# diode_keyboard.net
KiCad netlist of a schematic drawn in EAGLE
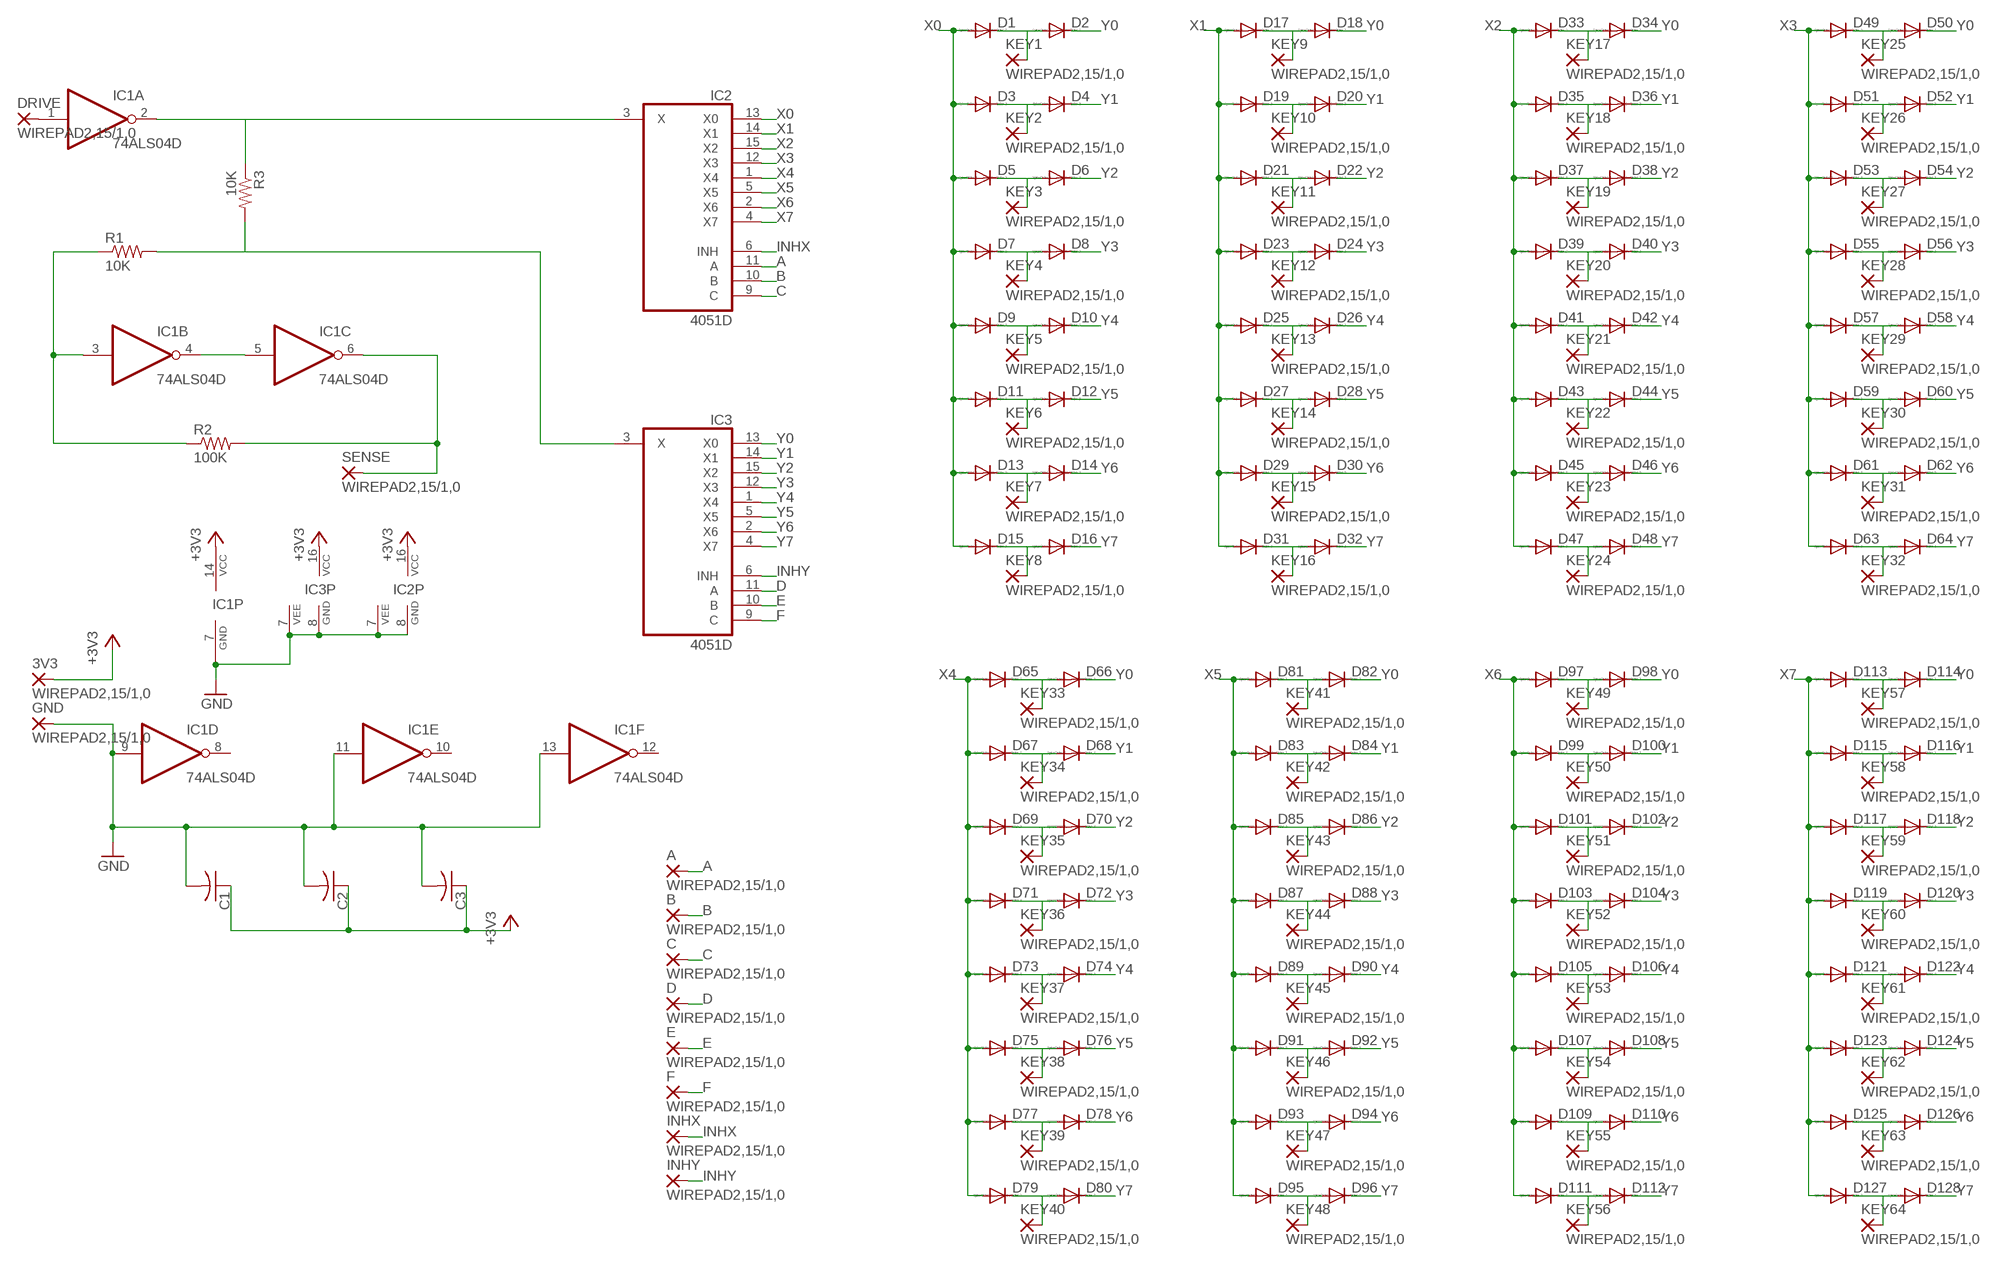
[diagram p0: schematic, sheet 1]

(export (version "E")
  (design (tool "Eeschema 10.0.6"))
  (components
    (comp (ref "3V3")
      (value "WIREPAD2,15/1,0")
      (footprint "eagle-import:2,15_1,0")
      (libsource (lib "eagle-import") (part "WIREPAD2,15/1,0"))
    )
    (comp (ref "A")
      (value "WIREPAD2,15/1,0")
      (footprint "eagle-import:2,15_1,0")
      (libsource (lib "eagle-import") (part "WIREPAD2,15/1,0"))
    )
    (comp (ref "B")
      (value "WIREPAD2,15/1,0")
      (footprint "eagle-import:2,15_1,0")
      (libsource (lib "eagle-import") (part "WIREPAD2,15/1,0"))
    )
    (comp (ref "C")
      (value "WIREPAD2,15/1,0")
      (footprint "eagle-import:2,15_1,0")
      (libsource (lib "eagle-import") (part "WIREPAD2,15/1,0"))
    )
    (comp (ref "C1")
      (value "C-US025-024X044")
      (footprint "eagle-import:C025-024X044")
      (libsource (lib "eagle-import") (part "C-US025-024X044"))
    )
    (comp (ref "C2")
      (value "C-US025-024X044")
      (footprint "eagle-import:C025-024X044")
      (libsource (lib "eagle-import") (part "C-US025-024X044"))
    )
    (comp (ref "C3")
      (value "C-US025-024X044")
      (footprint "eagle-import:C025-024X044")
      (libsource (lib "eagle-import") (part "C-US025-024X044"))
    )
    (comp (ref "D")
      (value "WIREPAD2,15/1,0")
      (footprint "eagle-import:2,15_1,0")
      (libsource (lib "eagle-import") (part "WIREPAD2,15/1,0"))
    )
    (comp (ref "D1")
      (value "DIODE-D-2.5")
      (footprint "eagle-import:D-2.5")
      (libsource (lib "eagle-import") (part "DIODE-D-2.5"))
    )
    (comp (ref "D2")
      (value "DIODE-D-2.5")
      (footprint "eagle-import:D-2.5")
      (libsource (lib "eagle-import") (part "DIODE-D-2.5"))
    )
    (comp (ref "D3")
      (value "DIODE-D-2.5")
      (footprint "eagle-import:D-2.5")
      (libsource (lib "eagle-import") (part "DIODE-D-2.5"))
    )
    (comp (ref "D4")
      (value "DIODE-D-2.5")
      (footprint "eagle-import:D-2.5")
      (libsource (lib "eagle-import") (part "DIODE-D-2.5"))
    )
    (comp (ref "D5")
      (value "DIODE-D-2.5")
      (footprint "eagle-import:D-2.5")
      (libsource (lib "eagle-import") (part "DIODE-D-2.5"))
    )
    (comp (ref "D6")
      (value "DIODE-D-2.5")
      (footprint "eagle-import:D-2.5")
      (libsource (lib "eagle-import") (part "DIODE-D-2.5"))
    )
    (comp (ref "D7")
      (value "DIODE-D-2.5")
      (footprint "eagle-import:D-2.5")
      (libsource (lib "eagle-import") (part "DIODE-D-2.5"))
    )
    (comp (ref "D8")
      (value "DIODE-D-2.5")
      (footprint "eagle-import:D-2.5")
      (libsource (lib "eagle-import") (part "DIODE-D-2.5"))
    )
    (comp (ref "D9")
      (value "DIODE-D-2.5")
      (footprint "eagle-import:D-2.5")
      (libsource (lib "eagle-import") (part "DIODE-D-2.5"))
    )
    (comp (ref "D10")
      (value "DIODE-D-2.5")
      (footprint "eagle-import:D-2.5")
      (libsource (lib "eagle-import") (part "DIODE-D-2.5"))
    )
    (comp (ref "D11")
      (value "DIODE-D-2.5")
      (footprint "eagle-import:D-2.5")
      (libsource (lib "eagle-import") (part "DIODE-D-2.5"))
    )
    (comp (ref "D12")
      (value "DIODE-D-2.5")
      (footprint "eagle-import:D-2.5")
      (libsource (lib "eagle-import") (part "DIODE-D-2.5"))
    )
    (comp (ref "D13")
      (value "DIODE-D-2.5")
      (footprint "eagle-import:D-2.5")
      (libsource (lib "eagle-import") (part "DIODE-D-2.5"))
    )
    (comp (ref "D14")
      (value "DIODE-D-2.5")
      (footprint "eagle-import:D-2.5")
      (libsource (lib "eagle-import") (part "DIODE-D-2.5"))
    )
    (comp (ref "D15")
      (value "DIODE-D-2.5")
      (footprint "eagle-import:D-2.5")
      (libsource (lib "eagle-import") (part "DIODE-D-2.5"))
    )
    (comp (ref "D16")
      (value "DIODE-D-2.5")
      (footprint "eagle-import:D-2.5")
      (libsource (lib "eagle-import") (part "DIODE-D-2.5"))
    )
    (comp (ref "D17")
      (value "DIODE-D-2.5")
      (footprint "eagle-import:D-2.5")
      (libsource (lib "eagle-import") (part "DIODE-D-2.5"))
    )
    (comp (ref "D18")
      (value "DIODE-D-2.5")
      (footprint "eagle-import:D-2.5")
      (libsource (lib "eagle-import") (part "DIODE-D-2.5"))
    )
    (comp (ref "D19")
      (value "DIODE-D-2.5")
      (footprint "eagle-import:D-2.5")
      (libsource (lib "eagle-import") (part "DIODE-D-2.5"))
    )
    (comp (ref "D20")
      (value "DIODE-D-2.5")
      (footprint "eagle-import:D-2.5")
      (libsource (lib "eagle-import") (part "DIODE-D-2.5"))
    )
    (comp (ref "D21")
      (value "DIODE-D-2.5")
      (footprint "eagle-import:D-2.5")
      (libsource (lib "eagle-import") (part "DIODE-D-2.5"))
    )
    (comp (ref "D22")
      (value "DIODE-D-2.5")
      (footprint "eagle-import:D-2.5")
      (libsource (lib "eagle-import") (part "DIODE-D-2.5"))
    )
    (comp (ref "D23")
      (value "DIODE-D-2.5")
      (footprint "eagle-import:D-2.5")
      (libsource (lib "eagle-import") (part "DIODE-D-2.5"))
    )
    (comp (ref "D24")
      (value "DIODE-D-2.5")
      (footprint "eagle-import:D-2.5")
      (libsource (lib "eagle-import") (part "DIODE-D-2.5"))
    )
    (comp (ref "D25")
      (value "DIODE-D-2.5")
      (footprint "eagle-import:D-2.5")
      (libsource (lib "eagle-import") (part "DIODE-D-2.5"))
    )
    (comp (ref "D26")
      (value "DIODE-D-2.5")
      (footprint "eagle-import:D-2.5")
      (libsource (lib "eagle-import") (part "DIODE-D-2.5"))
    )
    (comp (ref "D27")
      (value "DIODE-D-2.5")
      (footprint "eagle-import:D-2.5")
      (libsource (lib "eagle-import") (part "DIODE-D-2.5"))
    )
    (comp (ref "D28")
      (value "DIODE-D-2.5")
      (footprint "eagle-import:D-2.5")
      (libsource (lib "eagle-import") (part "DIODE-D-2.5"))
    )
    (comp (ref "D29")
      (value "DIODE-D-2.5")
      (footprint "eagle-import:D-2.5")
      (libsource (lib "eagle-import") (part "DIODE-D-2.5"))
    )
    (comp (ref "D30")
      (value "DIODE-D-2.5")
      (footprint "eagle-import:D-2.5")
      (libsource (lib "eagle-import") (part "DIODE-D-2.5"))
    )
    (comp (ref "D31")
      (value "DIODE-D-2.5")
      (footprint "eagle-import:D-2.5")
      (libsource (lib "eagle-import") (part "DIODE-D-2.5"))
    )
    (comp (ref "D32")
      (value "DIODE-D-2.5")
      (footprint "eagle-import:D-2.5")
      (libsource (lib "eagle-import") (part "DIODE-D-2.5"))
    )
    (comp (ref "D33")
      (value "DIODE-D-2.5")
      (footprint "eagle-import:D-2.5")
      (libsource (lib "eagle-import") (part "DIODE-D-2.5"))
    )
    (comp (ref "D34")
      (value "DIODE-D-2.5")
      (footprint "eagle-import:D-2.5")
      (libsource (lib "eagle-import") (part "DIODE-D-2.5"))
    )
    (comp (ref "D35")
      (value "DIODE-D-2.5")
      (footprint "eagle-import:D-2.5")
      (libsource (lib "eagle-import") (part "DIODE-D-2.5"))
    )
    (comp (ref "D36")
      (value "DIODE-D-2.5")
      (footprint "eagle-import:D-2.5")
      (libsource (lib "eagle-import") (part "DIODE-D-2.5"))
    )
    (comp (ref "D37")
      (value "DIODE-D-2.5")
      (footprint "eagle-import:D-2.5")
      (libsource (lib "eagle-import") (part "DIODE-D-2.5"))
    )
    (comp (ref "D38")
      (value "DIODE-D-2.5")
      (footprint "eagle-import:D-2.5")
      (libsource (lib "eagle-import") (part "DIODE-D-2.5"))
    )
    (comp (ref "D39")
      (value "DIODE-D-2.5")
      (footprint "eagle-import:D-2.5")
      (libsource (lib "eagle-import") (part "DIODE-D-2.5"))
    )
    (comp (ref "D40")
      (value "DIODE-D-2.5")
      (footprint "eagle-import:D-2.5")
      (libsource (lib "eagle-import") (part "DIODE-D-2.5"))
    )
    (comp (ref "D41")
      (value "DIODE-D-2.5")
      (footprint "eagle-import:D-2.5")
      (libsource (lib "eagle-import") (part "DIODE-D-2.5"))
    )
    (comp (ref "D42")
      (value "DIODE-D-2.5")
      (footprint "eagle-import:D-2.5")
      (libsource (lib "eagle-import") (part "DIODE-D-2.5"))
    )
    (comp (ref "D43")
      (value "DIODE-D-2.5")
      (footprint "eagle-import:D-2.5")
      (libsource (lib "eagle-import") (part "DIODE-D-2.5"))
    )
    (comp (ref "D44")
      (value "DIODE-D-2.5")
      (footprint "eagle-import:D-2.5")
      (libsource (lib "eagle-import") (part "DIODE-D-2.5"))
    )
    (comp (ref "D45")
      (value "DIODE-D-2.5")
      (footprint "eagle-import:D-2.5")
      (libsource (lib "eagle-import") (part "DIODE-D-2.5"))
    )
    (comp (ref "D46")
      (value "DIODE-D-2.5")
      (footprint "eagle-import:D-2.5")
      (libsource (lib "eagle-import") (part "DIODE-D-2.5"))
    )
    (comp (ref "D47")
      (value "DIODE-D-2.5")
      (footprint "eagle-import:D-2.5")
      (libsource (lib "eagle-import") (part "DIODE-D-2.5"))
    )
    (comp (ref "D48")
      (value "DIODE-D-2.5")
      (footprint "eagle-import:D-2.5")
      (libsource (lib "eagle-import") (part "DIODE-D-2.5"))
    )
    (comp (ref "D49")
      (value "DIODE-D-2.5")
      (footprint "eagle-import:D-2.5")
      (libsource (lib "eagle-import") (part "DIODE-D-2.5"))
    )
    (comp (ref "D50")
      (value "DIODE-D-2.5")
      (footprint "eagle-import:D-2.5")
      (libsource (lib "eagle-import") (part "DIODE-D-2.5"))
    )
    (comp (ref "D51")
      (value "DIODE-D-2.5")
      (footprint "eagle-import:D-2.5")
      (libsource (lib "eagle-import") (part "DIODE-D-2.5"))
    )
    (comp (ref "D52")
      (value "DIODE-D-2.5")
      (footprint "eagle-import:D-2.5")
      (libsource (lib "eagle-import") (part "DIODE-D-2.5"))
    )
    (comp (ref "D53")
      (value "DIODE-D-2.5")
      (footprint "eagle-import:D-2.5")
      (libsource (lib "eagle-import") (part "DIODE-D-2.5"))
    )
    (comp (ref "D54")
      (value "DIODE-D-2.5")
      (footprint "eagle-import:D-2.5")
      (libsource (lib "eagle-import") (part "DIODE-D-2.5"))
    )
    (comp (ref "D55")
      (value "DIODE-D-2.5")
      (footprint "eagle-import:D-2.5")
      (libsource (lib "eagle-import") (part "DIODE-D-2.5"))
    )
    (comp (ref "D56")
      (value "DIODE-D-2.5")
      (footprint "eagle-import:D-2.5")
      (libsource (lib "eagle-import") (part "DIODE-D-2.5"))
    )
    (comp (ref "D57")
      (value "DIODE-D-2.5")
      (footprint "eagle-import:D-2.5")
      (libsource (lib "eagle-import") (part "DIODE-D-2.5"))
    )
    (comp (ref "D58")
      (value "DIODE-D-2.5")
      (footprint "eagle-import:D-2.5")
      (libsource (lib "eagle-import") (part "DIODE-D-2.5"))
    )
    (comp (ref "D59")
      (value "DIODE-D-2.5")
      (footprint "eagle-import:D-2.5")
      (libsource (lib "eagle-import") (part "DIODE-D-2.5"))
    )
    (comp (ref "D60")
      (value "DIODE-D-2.5")
      (footprint "eagle-import:D-2.5")
      (libsource (lib "eagle-import") (part "DIODE-D-2.5"))
    )
    (comp (ref "D61")
      (value "DIODE-D-2.5")
      (footprint "eagle-import:D-2.5")
      (libsource (lib "eagle-import") (part "DIODE-D-2.5"))
    )
    (comp (ref "D62")
      (value "DIODE-D-2.5")
      (footprint "eagle-import:D-2.5")
      (libsource (lib "eagle-import") (part "DIODE-D-2.5"))
    )
    (comp (ref "D63")
      (value "DIODE-D-2.5")
      (footprint "eagle-import:D-2.5")
      (libsource (lib "eagle-import") (part "DIODE-D-2.5"))
    )
    (comp (ref "D64")
      (value "DIODE-D-2.5")
      (footprint "eagle-import:D-2.5")
      (libsource (lib "eagle-import") (part "DIODE-D-2.5"))
    )
    (comp (ref "D65")
      (value "DIODE-D-2.5")
      (footprint "eagle-import:D-2.5")
      (libsource (lib "eagle-import") (part "DIODE-D-2.5"))
    )
    (comp (ref "D66")
      (value "DIODE-D-2.5")
      (footprint "eagle-import:D-2.5")
      (libsource (lib "eagle-import") (part "DIODE-D-2.5"))
    )
    (comp (ref "D67")
      (value "DIODE-D-2.5")
      (footprint "eagle-import:D-2.5")
      (libsource (lib "eagle-import") (part "DIODE-D-2.5"))
    )
    (comp (ref "D68")
      (value "DIODE-D-2.5")
      (footprint "eagle-import:D-2.5")
      (libsource (lib "eagle-import") (part "DIODE-D-2.5"))
    )
    (comp (ref "D69")
      (value "DIODE-D-2.5")
      (footprint "eagle-import:D-2.5")
      (libsource (lib "eagle-import") (part "DIODE-D-2.5"))
    )
    (comp (ref "D70")
      (value "DIODE-D-2.5")
      (footprint "eagle-import:D-2.5")
      (libsource (lib "eagle-import") (part "DIODE-D-2.5"))
    )
    (comp (ref "D71")
      (value "DIODE-D-2.5")
      (footprint "eagle-import:D-2.5")
      (libsource (lib "eagle-import") (part "DIODE-D-2.5"))
    )
    (comp (ref "D72")
      (value "DIODE-D-2.5")
      (footprint "eagle-import:D-2.5")
      (libsource (lib "eagle-import") (part "DIODE-D-2.5"))
    )
    (comp (ref "D73")
      (value "DIODE-D-2.5")
      (footprint "eagle-import:D-2.5")
      (libsource (lib "eagle-import") (part "DIODE-D-2.5"))
    )
    (comp (ref "D74")
      (value "DIODE-D-2.5")
      (footprint "eagle-import:D-2.5")
      (libsource (lib "eagle-import") (part "DIODE-D-2.5"))
    )
    (comp (ref "D75")
      (value "DIODE-D-2.5")
      (footprint "eagle-import:D-2.5")
      (libsource (lib "eagle-import") (part "DIODE-D-2.5"))
    )
    (comp (ref "D76")
      (value "DIODE-D-2.5")
      (footprint "eagle-import:D-2.5")
      (libsource (lib "eagle-import") (part "DIODE-D-2.5"))
    )
    (comp (ref "D77")
      (value "DIODE-D-2.5")
      (footprint "eagle-import:D-2.5")
      (libsource (lib "eagle-import") (part "DIODE-D-2.5"))
    )
    (comp (ref "D78")
      (value "DIODE-D-2.5")
      (footprint "eagle-import:D-2.5")
      (libsource (lib "eagle-import") (part "DIODE-D-2.5"))
    )
    (comp (ref "D79")
      (value "DIODE-D-2.5")
      (footprint "eagle-import:D-2.5")
      (libsource (lib "eagle-import") (part "DIODE-D-2.5"))
    )
    (comp (ref "D80")
      (value "DIODE-D-2.5")
      (footprint "eagle-import:D-2.5")
      (libsource (lib "eagle-import") (part "DIODE-D-2.5"))
    )
    (comp (ref "D81")
      (value "DIODE-D-2.5")
      (footprint "eagle-import:D-2.5")
      (libsource (lib "eagle-import") (part "DIODE-D-2.5"))
    )
    (comp (ref "D82")
      (value "DIODE-D-2.5")
      (footprint "eagle-import:D-2.5")
      (libsource (lib "eagle-import") (part "DIODE-D-2.5"))
    )
    (comp (ref "D83")
      (value "DIODE-D-2.5")
      (footprint "eagle-import:D-2.5")
      (libsource (lib "eagle-import") (part "DIODE-D-2.5"))
    )
    (comp (ref "D84")
      (value "DIODE-D-2.5")
      (footprint "eagle-import:D-2.5")
      (libsource (lib "eagle-import") (part "DIODE-D-2.5"))
    )
    (comp (ref "D85")
      (value "DIODE-D-2.5")
      (footprint "eagle-import:D-2.5")
      (libsource (lib "eagle-import") (part "DIODE-D-2.5"))
    )
    (comp (ref "D86")
      (value "DIODE-D-2.5")
      (footprint "eagle-import:D-2.5")
      (libsource (lib "eagle-import") (part "DIODE-D-2.5"))
    )
    (comp (ref "D87")
      (value "DIODE-D-2.5")
      (footprint "eagle-import:D-2.5")
      (libsource (lib "eagle-import") (part "DIODE-D-2.5"))
    )
    (comp (ref "D88")
      (value "DIODE-D-2.5")
      (footprint "eagle-import:D-2.5")
      (libsource (lib "eagle-import") (part "DIODE-D-2.5"))
    )
    (comp (ref "D89")
      (value "DIODE-D-2.5")
      (footprint "eagle-import:D-2.5")
      (libsource (lib "eagle-import") (part "DIODE-D-2.5"))
    )
    (comp (ref "D90")
      (value "DIODE-D-2.5")
      (footprint "eagle-import:D-2.5")
      (libsource (lib "eagle-import") (part "DIODE-D-2.5"))
    )
    (comp (ref "D91")
      (value "DIODE-D-2.5")
      (footprint "eagle-import:D-2.5")
      (libsource (lib "eagle-import") (part "DIODE-D-2.5"))
    )
    (comp (ref "D92")
      (value "DIODE-D-2.5")
      (footprint "eagle-import:D-2.5")
      (libsource (lib "eagle-import") (part "DIODE-D-2.5"))
    )
    (comp (ref "D93")
      (value "DIODE-D-2.5")
      (footprint "eagle-import:D-2.5")
      (libsource (lib "eagle-import") (part "DIODE-D-2.5"))
    )
    (comp (ref "D94")
      (value "DIODE-D-2.5")
      (footprint "eagle-import:D-2.5")
      (libsource (lib "eagle-import") (part "DIODE-D-2.5"))
    )
    (comp (ref "D95")
      (value "DIODE-D-2.5")
      (footprint "eagle-import:D-2.5")
      (libsource (lib "eagle-import") (part "DIODE-D-2.5"))
    )
    (comp (ref "D96")
      (value "DIODE-D-2.5")
      (footprint "eagle-import:D-2.5")
      (libsource (lib "eagle-import") (part "DIODE-D-2.5"))
    )
    (comp (ref "D97")
      (value "DIODE-D-2.5")
      (footprint "eagle-import:D-2.5")
      (libsource (lib "eagle-import") (part "DIODE-D-2.5"))
    )
    (comp (ref "D98")
      (value "DIODE-D-2.5")
      (footprint "eagle-import:D-2.5")
      (libsource (lib "eagle-import") (part "DIODE-D-2.5"))
    )
    (comp (ref "D99")
      (value "DIODE-D-2.5")
      (footprint "eagle-import:D-2.5")
      (libsource (lib "eagle-import") (part "DIODE-D-2.5"))
    )
    (comp (ref "D100")
      (value "DIODE-D-2.5")
      (footprint "eagle-import:D-2.5")
      (libsource (lib "eagle-import") (part "DIODE-D-2.5"))
    )
    (comp (ref "D101")
      (value "DIODE-D-2.5")
      (footprint "eagle-import:D-2.5")
      (libsource (lib "eagle-import") (part "DIODE-D-2.5"))
    )
    (comp (ref "D102")
      (value "DIODE-D-2.5")
      (footprint "eagle-import:D-2.5")
      (libsource (lib "eagle-import") (part "DIODE-D-2.5"))
    )
    (comp (ref "D103")
      (value "DIODE-D-2.5")
      (footprint "eagle-import:D-2.5")
      (libsource (lib "eagle-import") (part "DIODE-D-2.5"))
    )
    (comp (ref "D104")
      (value "DIODE-D-2.5")
      (footprint "eagle-import:D-2.5")
      (libsource (lib "eagle-import") (part "DIODE-D-2.5"))
    )
    (comp (ref "D105")
      (value "DIODE-D-2.5")
      (footprint "eagle-import:D-2.5")
      (libsource (lib "eagle-import") (part "DIODE-D-2.5"))
    )
    (comp (ref "D106")
      (value "DIODE-D-2.5")
      (footprint "eagle-import:D-2.5")
      (libsource (lib "eagle-import") (part "DIODE-D-2.5"))
    )
    (comp (ref "D107")
      (value "DIODE-D-2.5")
      (footprint "eagle-import:D-2.5")
      (libsource (lib "eagle-import") (part "DIODE-D-2.5"))
    )
    (comp (ref "D108")
      (value "DIODE-D-2.5")
      (footprint "eagle-import:D-2.5")
      (libsource (lib "eagle-import") (part "DIODE-D-2.5"))
    )
    (comp (ref "D109")
      (value "DIODE-D-2.5")
      (footprint "eagle-import:D-2.5")
      (libsource (lib "eagle-import") (part "DIODE-D-2.5"))
    )
    (comp (ref "D110")
      (value "DIODE-D-2.5")
      (footprint "eagle-import:D-2.5")
      (libsource (lib "eagle-import") (part "DIODE-D-2.5"))
    )
    (comp (ref "D111")
      (value "DIODE-D-2.5")
      (footprint "eagle-import:D-2.5")
      (libsource (lib "eagle-import") (part "DIODE-D-2.5"))
    )
    (comp (ref "D112")
      (value "DIODE-D-2.5")
      (footprint "eagle-import:D-2.5")
      (libsource (lib "eagle-import") (part "DIODE-D-2.5"))
    )
    (comp (ref "D113")
      (value "DIODE-D-2.5")
      (footprint "eagle-import:D-2.5")
      (libsource (lib "eagle-import") (part "DIODE-D-2.5"))
    )
    (comp (ref "D114")
      (value "DIODE-D-2.5")
      (footprint "eagle-import:D-2.5")
      (libsource (lib "eagle-import") (part "DIODE-D-2.5"))
    )
    (comp (ref "D115")
      (value "DIODE-D-2.5")
      (footprint "eagle-import:D-2.5")
      (libsource (lib "eagle-import") (part "DIODE-D-2.5"))
    )
    (comp (ref "D116")
      (value "DIODE-D-2.5")
      (footprint "eagle-import:D-2.5")
      (libsource (lib "eagle-import") (part "DIODE-D-2.5"))
    )
    (comp (ref "D117")
      (value "DIODE-D-2.5")
      (footprint "eagle-import:D-2.5")
      (libsource (lib "eagle-import") (part "DIODE-D-2.5"))
    )
    (comp (ref "D118")
      (value "DIODE-D-2.5")
      (footprint "eagle-import:D-2.5")
      (libsource (lib "eagle-import") (part "DIODE-D-2.5"))
    )
    (comp (ref "D119")
      (value "DIODE-D-2.5")
      (footprint "eagle-import:D-2.5")
      (libsource (lib "eagle-import") (part "DIODE-D-2.5"))
    )
    (comp (ref "D120")
      (value "DIODE-D-2.5")
      (footprint "eagle-import:D-2.5")
      (libsource (lib "eagle-import") (part "DIODE-D-2.5"))
    )
    (comp (ref "D121")
      (value "DIODE-D-2.5")
      (footprint "eagle-import:D-2.5")
      (libsource (lib "eagle-import") (part "DIODE-D-2.5"))
    )
    (comp (ref "D122")
      (value "DIODE-D-2.5")
      (footprint "eagle-import:D-2.5")
      (libsource (lib "eagle-import") (part "DIODE-D-2.5"))
    )
    (comp (ref "D123")
      (value "DIODE-D-2.5")
      (footprint "eagle-import:D-2.5")
      (libsource (lib "eagle-import") (part "DIODE-D-2.5"))
    )
    (comp (ref "D124")
      (value "DIODE-D-2.5")
      (footprint "eagle-import:D-2.5")
      (libsource (lib "eagle-import") (part "DIODE-D-2.5"))
    )
    (comp (ref "D125")
      (value "DIODE-D-2.5")
      (footprint "eagle-import:D-2.5")
      (libsource (lib "eagle-import") (part "DIODE-D-2.5"))
    )
    (comp (ref "D126")
      (value "DIODE-D-2.5")
      (footprint "eagle-import:D-2.5")
      (libsource (lib "eagle-import") (part "DIODE-D-2.5"))
    )
    (comp (ref "D127")
      (value "DIODE-D-2.5")
      (footprint "eagle-import:D-2.5")
      (libsource (lib "eagle-import") (part "DIODE-D-2.5"))
    )
    (comp (ref "D128")
      (value "DIODE-D-2.5")
      (footprint "eagle-import:D-2.5")
      (libsource (lib "eagle-import") (part "DIODE-D-2.5"))
    )
    (comp (ref "DRIVE")
      (value "WIREPAD2,15/1,0")
      (footprint "eagle-import:2,15_1,0")
      (libsource (lib "eagle-import") (part "WIREPAD2,15/1,0"))
    )
    (comp (ref "E")
      (value "WIREPAD2,15/1,0")
      (footprint "eagle-import:2,15_1,0")
      (libsource (lib "eagle-import") (part "WIREPAD2,15/1,0"))
    )
    (comp (ref "F")
      (value "WIREPAD2,15/1,0")
      (footprint "eagle-import:2,15_1,0")
      (libsource (lib "eagle-import") (part "WIREPAD2,15/1,0"))
    )
    (comp (ref "GND")
      (value "WIREPAD2,15/1,0")
      (footprint "eagle-import:2,15_1,0")
      (libsource (lib "eagle-import") (part "WIREPAD2,15/1,0"))
    )
    (comp (ref "IC1")
      (value "74ALS04D")
      (footprint "eagle-import:SO14")
      (libsource (lib "eagle-import") (part "7404DALS"))
    )
    (comp (ref "IC2")
      (value "4051D")
      (footprint "eagle-import:SO16")
      (libsource (lib "eagle-import") (part "4051D"))
    )
    (comp (ref "IC3")
      (value "4051D")
      (footprint "eagle-import:SO16")
      (libsource (lib "eagle-import") (part "4051D"))
    )
    (comp (ref "INHX")
      (value "WIREPAD2,15/1,0")
      (footprint "eagle-import:2,15_1,0")
      (libsource (lib "eagle-import") (part "WIREPAD2,15/1,0"))
    )
    (comp (ref "INHY")
      (value "WIREPAD2,15/1,0")
      (footprint "eagle-import:2,15_1,0")
      (libsource (lib "eagle-import") (part "WIREPAD2,15/1,0"))
    )
    (comp (ref "KEY1")
      (value "WIREPAD2,15/1,0")
      (footprint "eagle-import:2,15_1,0")
      (libsource (lib "eagle-import") (part "WIREPAD2,15/1,0"))
    )
    (comp (ref "KEY2")
      (value "WIREPAD2,15/1,0")
      (footprint "eagle-import:2,15_1,0")
      (libsource (lib "eagle-import") (part "WIREPAD2,15/1,0"))
    )
    (comp (ref "KEY3")
      (value "WIREPAD2,15/1,0")
      (footprint "eagle-import:2,15_1,0")
      (libsource (lib "eagle-import") (part "WIREPAD2,15/1,0"))
    )
    (comp (ref "KEY4")
      (value "WIREPAD2,15/1,0")
      (footprint "eagle-import:2,15_1,0")
      (libsource (lib "eagle-import") (part "WIREPAD2,15/1,0"))
    )
    (comp (ref "KEY5")
      (value "WIREPAD2,15/1,0")
      (footprint "eagle-import:2,15_1,0")
      (libsource (lib "eagle-import") (part "WIREPAD2,15/1,0"))
    )
    (comp (ref "KEY6")
      (value "WIREPAD2,15/1,0")
      (footprint "eagle-import:2,15_1,0")
      (libsource (lib "eagle-import") (part "WIREPAD2,15/1,0"))
    )
    (comp (ref "KEY7")
      (value "WIREPAD2,15/1,0")
      (footprint "eagle-import:2,15_1,0")
      (libsource (lib "eagle-import") (part "WIREPAD2,15/1,0"))
    )
    (comp (ref "KEY8")
      (value "WIREPAD2,15/1,0")
      (footprint "eagle-import:2,15_1,0")
      (libsource (lib "eagle-import") (part "WIREPAD2,15/1,0"))
    )
    (comp (ref "KEY9")
      (value "WIREPAD2,15/1,0")
      (footprint "eagle-import:2,15_1,0")
      (libsource (lib "eagle-import") (part "WIREPAD2,15/1,0"))
    )
    (comp (ref "KEY10")
      (value "WIREPAD2,15/1,0")
      (footprint "eagle-import:2,15_1,0")
      (libsource (lib "eagle-import") (part "WIREPAD2,15/1,0"))
    )
    (comp (ref "KEY11")
      (value "WIREPAD2,15/1,0")
      (footprint "eagle-import:2,15_1,0")
      (libsource (lib "eagle-import") (part "WIREPAD2,15/1,0"))
    )
    (comp (ref "KEY12")
      (value "WIREPAD2,15/1,0")
      (footprint "eagle-import:2,15_1,0")
      (libsource (lib "eagle-import") (part "WIREPAD2,15/1,0"))
    )
    (comp (ref "KEY13")
      (value "WIREPAD2,15/1,0")
      (footprint "eagle-import:2,15_1,0")
      (libsource (lib "eagle-import") (part "WIREPAD2,15/1,0"))
    )
    (comp (ref "KEY14")
      (value "WIREPAD2,15/1,0")
      (footprint "eagle-import:2,15_1,0")
      (libsource (lib "eagle-import") (part "WIREPAD2,15/1,0"))
    )
    (comp (ref "KEY15")
      (value "WIREPAD2,15/1,0")
      (footprint "eagle-import:2,15_1,0")
      (libsource (lib "eagle-import") (part "WIREPAD2,15/1,0"))
    )
    (comp (ref "KEY16")
      (value "WIREPAD2,15/1,0")
      (footprint "eagle-import:2,15_1,0")
      (libsource (lib "eagle-import") (part "WIREPAD2,15/1,0"))
    )
    (comp (ref "KEY17")
      (value "WIREPAD2,15/1,0")
      (footprint "eagle-import:2,15_1,0")
      (libsource (lib "eagle-import") (part "WIREPAD2,15/1,0"))
    )
    (comp (ref "KEY18")
      (value "WIREPAD2,15/1,0")
      (footprint "eagle-import:2,15_1,0")
      (libsource (lib "eagle-import") (part "WIREPAD2,15/1,0"))
    )
    (comp (ref "KEY19")
      (value "WIREPAD2,15/1,0")
      (footprint "eagle-import:2,15_1,0")
      (libsource (lib "eagle-import") (part "WIREPAD2,15/1,0"))
    )
    (comp (ref "KEY20")
      (value "WIREPAD2,15/1,0")
      (footprint "eagle-import:2,15_1,0")
      (libsource (lib "eagle-import") (part "WIREPAD2,15/1,0"))
    )
    (comp (ref "KEY21")
      (value "WIREPAD2,15/1,0")
      (footprint "eagle-import:2,15_1,0")
      (libsource (lib "eagle-import") (part "WIREPAD2,15/1,0"))
    )
    (comp (ref "KEY22")
      (value "WIREPAD2,15/1,0")
      (footprint "eagle-import:2,15_1,0")
      (libsource (lib "eagle-import") (part "WIREPAD2,15/1,0"))
    )
    (comp (ref "KEY23")
      (value "WIREPAD2,15/1,0")
      (footprint "eagle-import:2,15_1,0")
      (libsource (lib "eagle-import") (part "WIREPAD2,15/1,0"))
    )
    (comp (ref "KEY24")
      (value "WIREPAD2,15/1,0")
      (footprint "eagle-import:2,15_1,0")
      (libsource (lib "eagle-import") (part "WIREPAD2,15/1,0"))
    )
    (comp (ref "KEY25")
      (value "WIREPAD2,15/1,0")
      (footprint "eagle-import:2,15_1,0")
      (libsource (lib "eagle-import") (part "WIREPAD2,15/1,0"))
    )
    (comp (ref "KEY26")
      (value "WIREPAD2,15/1,0")
      (footprint "eagle-import:2,15_1,0")
      (libsource (lib "eagle-import") (part "WIREPAD2,15/1,0"))
    )
    (comp (ref "KEY27")
      (value "WIREPAD2,15/1,0")
      (footprint "eagle-import:2,15_1,0")
      (libsource (lib "eagle-import") (part "WIREPAD2,15/1,0"))
    )
    (comp (ref "KEY28")
      (value "WIREPAD2,15/1,0")
      (footprint "eagle-import:2,15_1,0")
      (libsource (lib "eagle-import") (part "WIREPAD2,15/1,0"))
    )
    (comp (ref "KEY29")
      (value "WIREPAD2,15/1,0")
      (footprint "eagle-import:2,15_1,0")
      (libsource (lib "eagle-import") (part "WIREPAD2,15/1,0"))
    )
    (comp (ref "KEY30")
      (value "WIREPAD2,15/1,0")
      (footprint "eagle-import:2,15_1,0")
      (libsource (lib "eagle-import") (part "WIREPAD2,15/1,0"))
    )
    (comp (ref "KEY31")
      (value "WIREPAD2,15/1,0")
      (footprint "eagle-import:2,15_1,0")
      (libsource (lib "eagle-import") (part "WIREPAD2,15/1,0"))
    )
    (comp (ref "KEY32")
      (value "WIREPAD2,15/1,0")
      (footprint "eagle-import:2,15_1,0")
      (libsource (lib "eagle-import") (part "WIREPAD2,15/1,0"))
    )
    (comp (ref "KEY33")
      (value "WIREPAD2,15/1,0")
      (footprint "eagle-import:2,15_1,0")
      (libsource (lib "eagle-import") (part "WIREPAD2,15/1,0"))
    )
    (comp (ref "KEY34")
      (value "WIREPAD2,15/1,0")
      (footprint "eagle-import:2,15_1,0")
      (libsource (lib "eagle-import") (part "WIREPAD2,15/1,0"))
    )
    (comp (ref "KEY35")
      (value "WIREPAD2,15/1,0")
      (footprint "eagle-import:2,15_1,0")
      (libsource (lib "eagle-import") (part "WIREPAD2,15/1,0"))
    )
    (comp (ref "KEY36")
      (value "WIREPAD2,15/1,0")
      (footprint "eagle-import:2,15_1,0")
      (libsource (lib "eagle-import") (part "WIREPAD2,15/1,0"))
    )
    (comp (ref "KEY37")
      (value "WIREPAD2,15/1,0")
      (footprint "eagle-import:2,15_1,0")
      (libsource (lib "eagle-import") (part "WIREPAD2,15/1,0"))
    )
    (comp (ref "KEY38")
      (value "WIREPAD2,15/1,0")
      (footprint "eagle-import:2,15_1,0")
      (libsource (lib "eagle-import") (part "WIREPAD2,15/1,0"))
    )
    (comp (ref "KEY39")
      (value "WIREPAD2,15/1,0")
      (footprint "eagle-import:2,15_1,0")
      (libsource (lib "eagle-import") (part "WIREPAD2,15/1,0"))
    )
    (comp (ref "KEY40")
      (value "WIREPAD2,15/1,0")
      (footprint "eagle-import:2,15_1,0")
      (libsource (lib "eagle-import") (part "WIREPAD2,15/1,0"))
    )
    (comp (ref "KEY41")
      (value "WIREPAD2,15/1,0")
      (footprint "eagle-import:2,15_1,0")
      (libsource (lib "eagle-import") (part "WIREPAD2,15/1,0"))
    )
    (comp (ref "KEY42")
      (value "WIREPAD2,15/1,0")
      (footprint "eagle-import:2,15_1,0")
      (libsource (lib "eagle-import") (part "WIREPAD2,15/1,0"))
    )
    (comp (ref "KEY43")
      (value "WIREPAD2,15/1,0")
      (footprint "eagle-import:2,15_1,0")
      (libsource (lib "eagle-import") (part "WIREPAD2,15/1,0"))
    )
    (comp (ref "KEY44")
      (value "WIREPAD2,15/1,0")
      (footprint "eagle-import:2,15_1,0")
      (libsource (lib "eagle-import") (part "WIREPAD2,15/1,0"))
    )
    (comp (ref "KEY45")
      (value "WIREPAD2,15/1,0")
      (footprint "eagle-import:2,15_1,0")
      (libsource (lib "eagle-import") (part "WIREPAD2,15/1,0"))
    )
    (comp (ref "KEY46")
      (value "WIREPAD2,15/1,0")
      (footprint "eagle-import:2,15_1,0")
      (libsource (lib "eagle-import") (part "WIREPAD2,15/1,0"))
    )
    (comp (ref "KEY47")
      (value "WIREPAD2,15/1,0")
      (footprint "eagle-import:2,15_1,0")
      (libsource (lib "eagle-import") (part "WIREPAD2,15/1,0"))
    )
    (comp (ref "KEY48")
      (value "WIREPAD2,15/1,0")
      (footprint "eagle-import:2,15_1,0")
      (libsource (lib "eagle-import") (part "WIREPAD2,15/1,0"))
    )
    (comp (ref "KEY49")
      (value "WIREPAD2,15/1,0")
      (footprint "eagle-import:2,15_1,0")
      (libsource (lib "eagle-import") (part "WIREPAD2,15/1,0"))
    )
    (comp (ref "KEY50")
      (value "WIREPAD2,15/1,0")
      (footprint "eagle-import:2,15_1,0")
      (libsource (lib "eagle-import") (part "WIREPAD2,15/1,0"))
    )
    (comp (ref "KEY51")
      (value "WIREPAD2,15/1,0")
      (footprint "eagle-import:2,15_1,0")
      (libsource (lib "eagle-import") (part "WIREPAD2,15/1,0"))
    )
    (comp (ref "KEY52")
      (value "WIREPAD2,15/1,0")
      (footprint "eagle-import:2,15_1,0")
      (libsource (lib "eagle-import") (part "WIREPAD2,15/1,0"))
    )
    (comp (ref "KEY53")
      (value "WIREPAD2,15/1,0")
      (footprint "eagle-import:2,15_1,0")
      (libsource (lib "eagle-import") (part "WIREPAD2,15/1,0"))
    )
    (comp (ref "KEY54")
      (value "WIREPAD2,15/1,0")
      (footprint "eagle-import:2,15_1,0")
      (libsource (lib "eagle-import") (part "WIREPAD2,15/1,0"))
    )
    (comp (ref "KEY55")
      (value "WIREPAD2,15/1,0")
      (footprint "eagle-import:2,15_1,0")
      (libsource (lib "eagle-import") (part "WIREPAD2,15/1,0"))
    )
    (comp (ref "KEY56")
      (value "WIREPAD2,15/1,0")
      (footprint "eagle-import:2,15_1,0")
      (libsource (lib "eagle-import") (part "WIREPAD2,15/1,0"))
    )
    (comp (ref "KEY57")
      (value "WIREPAD2,15/1,0")
      (footprint "eagle-import:2,15_1,0")
      (libsource (lib "eagle-import") (part "WIREPAD2,15/1,0"))
    )
    (comp (ref "KEY58")
      (value "WIREPAD2,15/1,0")
      (footprint "eagle-import:2,15_1,0")
      (libsource (lib "eagle-import") (part "WIREPAD2,15/1,0"))
    )
    (comp (ref "KEY59")
      (value "WIREPAD2,15/1,0")
      (footprint "eagle-import:2,15_1,0")
      (libsource (lib "eagle-import") (part "WIREPAD2,15/1,0"))
    )
    (comp (ref "KEY60")
      (value "WIREPAD2,15/1,0")
      (footprint "eagle-import:2,15_1,0")
      (libsource (lib "eagle-import") (part "WIREPAD2,15/1,0"))
    )
    (comp (ref "KEY61")
      (value "WIREPAD2,15/1,0")
      (footprint "eagle-import:2,15_1,0")
      (libsource (lib "eagle-import") (part "WIREPAD2,15/1,0"))
    )
    (comp (ref "KEY62")
      (value "WIREPAD2,15/1,0")
      (footprint "eagle-import:2,15_1,0")
      (libsource (lib "eagle-import") (part "WIREPAD2,15/1,0"))
    )
    (comp (ref "KEY63")
      (value "WIREPAD2,15/1,0")
      (footprint "eagle-import:2,15_1,0")
      (libsource (lib "eagle-import") (part "WIREPAD2,15/1,0"))
    )
    (comp (ref "KEY64")
      (value "WIREPAD2,15/1,0")
      (footprint "eagle-import:2,15_1,0")
      (libsource (lib "eagle-import") (part "WIREPAD2,15/1,0"))
    )
    (comp (ref "R1")
      (value "10K")
      (footprint "eagle-import:0207_2V")
      (libsource (lib "eagle-import") (part "R-US_0207/2V"))
    )
    (comp (ref "R2")
      (value "100K")
      (footprint "eagle-import:0207_2V")
      (libsource (lib "eagle-import") (part "R-US_0207/2V"))
    )
    (comp (ref "R3")
      (value "10K")
      (footprint "eagle-import:0207_2V")
      (libsource (lib "eagle-import") (part "R-US_0207/2V"))
    )
    (comp (ref "SENSE")
      (value "WIREPAD2,15/1,0")
      (footprint "eagle-import:2,15_1,0")
      (libsource (lib "eagle-import") (part "WIREPAD2,15/1,0"))
    )
  )
  (nets
    (net (code "1") (name "+3V3") (class "Default")
      (node (ref "3V3") (pin "1") (pinfunction "P_1") (pintype "passive"))
      (node (ref "C1") (pin "1") (pinfunction "1_1") (pintype "passive"))
      (node (ref "C2") (pin "1") (pinfunction "1_1") (pintype "passive"))
      (node (ref "C3") (pin "1") (pinfunction "1_1") (pintype "passive"))
      (node (ref "IC1") (pin "14") (pinfunction "VCC_14") (pintype "power_in"))
      (node (ref "IC2") (pin "16") (pinfunction "VCC_16") (pintype "power_in"))
      (node (ref "IC3") (pin "16") (pinfunction "VCC_16") (pintype "power_in"))
    )
    (net (code "2") (name "/A") (class "Default")
      (node (ref "A") (pin "1") (pinfunction "P_1") (pintype "passive"))
      (node (ref "IC2") (pin "11") (pinfunction "A_11") (pintype "input"))
    )
    (net (code "3") (name "/B") (class "Default")
      (node (ref "B") (pin "1") (pinfunction "P_1") (pintype "passive"))
      (node (ref "IC2") (pin "10") (pinfunction "B_10") (pintype "input"))
    )
    (net (code "4") (name "/C") (class "Default")
      (node (ref "C") (pin "1") (pinfunction "P_1") (pintype "passive"))
      (node (ref "IC2") (pin "9") (pinfunction "C_9") (pintype "input"))
    )
    (net (code "5") (name "/D") (class "Default")
      (node (ref "D") (pin "1") (pinfunction "P_1") (pintype "passive"))
      (node (ref "IC3") (pin "11") (pinfunction "A_11") (pintype "input"))
    )
    (net (code "6") (name "/E") (class "Default")
      (node (ref "E") (pin "1") (pinfunction "P_1") (pintype "passive"))
      (node (ref "IC3") (pin "10") (pinfunction "B_10") (pintype "input"))
    )
    (net (code "7") (name "/F") (class "Default")
      (node (ref "F") (pin "1") (pinfunction "P_1") (pintype "passive"))
      (node (ref "IC3") (pin "9") (pinfunction "C_9") (pintype "input"))
    )
    (net (code "8") (name "/INHX") (class "Default")
      (node (ref "IC2") (pin "6") (pinfunction "INH_6") (pintype "input"))
      (node (ref "INHX") (pin "1") (pinfunction "P_1") (pintype "passive"))
    )
    (net (code "9") (name "/INHY") (class "Default")
      (node (ref "IC3") (pin "6") (pinfunction "INH_6") (pintype "input"))
      (node (ref "INHY") (pin "1") (pinfunction "P_1") (pintype "passive"))
    )
    (net (code "10") (name "/X0") (class "Default")
      (node (ref "D1") (pin "A") (pinfunction "A_A") (pintype "passive"))
      (node (ref "D11") (pin "A") (pinfunction "A_A") (pintype "passive"))
      (node (ref "D13") (pin "A") (pinfunction "A_A") (pintype "passive"))
      (node (ref "D15") (pin "A") (pinfunction "A_A") (pintype "passive"))
      (node (ref "D3") (pin "A") (pinfunction "A_A") (pintype "passive"))
      (node (ref "D5") (pin "A") (pinfunction "A_A") (pintype "passive"))
      (node (ref "D7") (pin "A") (pinfunction "A_A") (pintype "passive"))
      (node (ref "D9") (pin "A") (pinfunction "A_A") (pintype "passive"))
      (node (ref "IC2") (pin "13") (pinfunction "X0_13") (pintype "bidirectional"))
    )
    (net (code "11") (name "/X1") (class "Default")
      (node (ref "D17") (pin "A") (pinfunction "A_A") (pintype "passive"))
      (node (ref "D19") (pin "A") (pinfunction "A_A") (pintype "passive"))
      (node (ref "D21") (pin "A") (pinfunction "A_A") (pintype "passive"))
      (node (ref "D23") (pin "A") (pinfunction "A_A") (pintype "passive"))
      (node (ref "D25") (pin "A") (pinfunction "A_A") (pintype "passive"))
      (node (ref "D27") (pin "A") (pinfunction "A_A") (pintype "passive"))
      (node (ref "D29") (pin "A") (pinfunction "A_A") (pintype "passive"))
      (node (ref "D31") (pin "A") (pinfunction "A_A") (pintype "passive"))
      (node (ref "IC2") (pin "14") (pinfunction "X1_14") (pintype "bidirectional"))
    )
    (net (code "12") (name "/X2") (class "Default")
      (node (ref "D33") (pin "A") (pinfunction "A_A") (pintype "passive"))
      (node (ref "D35") (pin "A") (pinfunction "A_A") (pintype "passive"))
      (node (ref "D37") (pin "A") (pinfunction "A_A") (pintype "passive"))
      (node (ref "D39") (pin "A") (pinfunction "A_A") (pintype "passive"))
      (node (ref "D41") (pin "A") (pinfunction "A_A") (pintype "passive"))
      (node (ref "D43") (pin "A") (pinfunction "A_A") (pintype "passive"))
      (node (ref "D45") (pin "A") (pinfunction "A_A") (pintype "passive"))
      (node (ref "D47") (pin "A") (pinfunction "A_A") (pintype "passive"))
      (node (ref "IC2") (pin "15") (pinfunction "X2_15") (pintype "bidirectional"))
    )
    (net (code "13") (name "/X3") (class "Default")
      (node (ref "D49") (pin "A") (pinfunction "A_A") (pintype "passive"))
      (node (ref "D51") (pin "A") (pinfunction "A_A") (pintype "passive"))
      (node (ref "D53") (pin "A") (pinfunction "A_A") (pintype "passive"))
      (node (ref "D55") (pin "A") (pinfunction "A_A") (pintype "passive"))
      (node (ref "D57") (pin "A") (pinfunction "A_A") (pintype "passive"))
      (node (ref "D59") (pin "A") (pinfunction "A_A") (pintype "passive"))
      (node (ref "D61") (pin "A") (pinfunction "A_A") (pintype "passive"))
      (node (ref "D63") (pin "A") (pinfunction "A_A") (pintype "passive"))
      (node (ref "IC2") (pin "12") (pinfunction "X3_12") (pintype "bidirectional"))
    )
    (net (code "14") (name "/X4") (class "Default")
      (node (ref "D65") (pin "A") (pinfunction "A_A") (pintype "passive"))
      (node (ref "D67") (pin "A") (pinfunction "A_A") (pintype "passive"))
      (node (ref "D69") (pin "A") (pinfunction "A_A") (pintype "passive"))
      (node (ref "D71") (pin "A") (pinfunction "A_A") (pintype "passive"))
      (node (ref "D73") (pin "A") (pinfunction "A_A") (pintype "passive"))
      (node (ref "D75") (pin "A") (pinfunction "A_A") (pintype "passive"))
      (node (ref "D77") (pin "A") (pinfunction "A_A") (pintype "passive"))
      (node (ref "D79") (pin "A") (pinfunction "A_A") (pintype "passive"))
      (node (ref "IC2") (pin "1") (pinfunction "X4_1") (pintype "bidirectional"))
    )
    (net (code "15") (name "/X5") (class "Default")
      (node (ref "D81") (pin "A") (pinfunction "A_A") (pintype "passive"))
      (node (ref "D83") (pin "A") (pinfunction "A_A") (pintype "passive"))
      (node (ref "D85") (pin "A") (pinfunction "A_A") (pintype "passive"))
      (node (ref "D87") (pin "A") (pinfunction "A_A") (pintype "passive"))
      (node (ref "D89") (pin "A") (pinfunction "A_A") (pintype "passive"))
      (node (ref "D91") (pin "A") (pinfunction "A_A") (pintype "passive"))
      (node (ref "D93") (pin "A") (pinfunction "A_A") (pintype "passive"))
      (node (ref "D95") (pin "A") (pinfunction "A_A") (pintype "passive"))
      (node (ref "IC2") (pin "5") (pinfunction "X5_5") (pintype "bidirectional"))
    )
    (net (code "16") (name "/X6") (class "Default")
      (node (ref "D101") (pin "A") (pinfunction "A_A") (pintype "passive"))
      (node (ref "D103") (pin "A") (pinfunction "A_A") (pintype "passive"))
      (node (ref "D105") (pin "A") (pinfunction "A_A") (pintype "passive"))
      (node (ref "D107") (pin "A") (pinfunction "A_A") (pintype "passive"))
      (node (ref "D109") (pin "A") (pinfunction "A_A") (pintype "passive"))
      (node (ref "D111") (pin "A") (pinfunction "A_A") (pintype "passive"))
      (node (ref "D97") (pin "A") (pinfunction "A_A") (pintype "passive"))
      (node (ref "D99") (pin "A") (pinfunction "A_A") (pintype "passive"))
      (node (ref "IC2") (pin "2") (pinfunction "X6_2") (pintype "bidirectional"))
    )
    (net (code "17") (name "/X7") (class "Default")
      (node (ref "D113") (pin "A") (pinfunction "A_A") (pintype "passive"))
      (node (ref "D115") (pin "A") (pinfunction "A_A") (pintype "passive"))
      (node (ref "D117") (pin "A") (pinfunction "A_A") (pintype "passive"))
      (node (ref "D119") (pin "A") (pinfunction "A_A") (pintype "passive"))
      (node (ref "D121") (pin "A") (pinfunction "A_A") (pintype "passive"))
      (node (ref "D123") (pin "A") (pinfunction "A_A") (pintype "passive"))
      (node (ref "D125") (pin "A") (pinfunction "A_A") (pintype "passive"))
      (node (ref "D127") (pin "A") (pinfunction "A_A") (pintype "passive"))
      (node (ref "IC2") (pin "4") (pinfunction "X7_4") (pintype "bidirectional"))
    )
    (net (code "18") (name "/Y0") (class "Default")
      (node (ref "D114") (pin "C") (pinfunction "C_C") (pintype "passive"))
      (node (ref "D18") (pin "C") (pinfunction "C_C") (pintype "passive"))
      (node (ref "D2") (pin "C") (pinfunction "C_C") (pintype "passive"))
      (node (ref "D34") (pin "C") (pinfunction "C_C") (pintype "passive"))
      (node (ref "D50") (pin "C") (pinfunction "C_C") (pintype "passive"))
      (node (ref "D66") (pin "C") (pinfunction "C_C") (pintype "passive"))
      (node (ref "D82") (pin "C") (pinfunction "C_C") (pintype "passive"))
      (node (ref "D98") (pin "C") (pinfunction "C_C") (pintype "passive"))
      (node (ref "IC3") (pin "13") (pinfunction "X0_13") (pintype "bidirectional"))
    )
    (net (code "19") (name "/Y1") (class "Default")
      (node (ref "D100") (pin "C") (pinfunction "C_C") (pintype "passive"))
      (node (ref "D116") (pin "C") (pinfunction "C_C") (pintype "passive"))
      (node (ref "D20") (pin "C") (pinfunction "C_C") (pintype "passive"))
      (node (ref "D36") (pin "C") (pinfunction "C_C") (pintype "passive"))
      (node (ref "D4") (pin "C") (pinfunction "C_C") (pintype "passive"))
      (node (ref "D52") (pin "C") (pinfunction "C_C") (pintype "passive"))
      (node (ref "D68") (pin "C") (pinfunction "C_C") (pintype "passive"))
      (node (ref "D84") (pin "C") (pinfunction "C_C") (pintype "passive"))
      (node (ref "IC3") (pin "14") (pinfunction "X1_14") (pintype "bidirectional"))
    )
    (net (code "20") (name "/Y2") (class "Default")
      (node (ref "D102") (pin "C") (pinfunction "C_C") (pintype "passive"))
      (node (ref "D118") (pin "C") (pinfunction "C_C") (pintype "passive"))
      (node (ref "D22") (pin "C") (pinfunction "C_C") (pintype "passive"))
      (node (ref "D38") (pin "C") (pinfunction "C_C") (pintype "passive"))
      (node (ref "D54") (pin "C") (pinfunction "C_C") (pintype "passive"))
      (node (ref "D6") (pin "C") (pinfunction "C_C") (pintype "passive"))
      (node (ref "D70") (pin "C") (pinfunction "C_C") (pintype "passive"))
      (node (ref "D86") (pin "C") (pinfunction "C_C") (pintype "passive"))
      (node (ref "IC3") (pin "15") (pinfunction "X2_15") (pintype "bidirectional"))
    )
    (net (code "21") (name "/Y3") (class "Default")
      (node (ref "D104") (pin "C") (pinfunction "C_C") (pintype "passive"))
      (node (ref "D120") (pin "C") (pinfunction "C_C") (pintype "passive"))
      (node (ref "D24") (pin "C") (pinfunction "C_C") (pintype "passive"))
      (node (ref "D40") (pin "C") (pinfunction "C_C") (pintype "passive"))
      (node (ref "D56") (pin "C") (pinfunction "C_C") (pintype "passive"))
      (node (ref "D72") (pin "C") (pinfunction "C_C") (pintype "passive"))
      (node (ref "D8") (pin "C") (pinfunction "C_C") (pintype "passive"))
      (node (ref "D88") (pin "C") (pinfunction "C_C") (pintype "passive"))
      (node (ref "IC3") (pin "12") (pinfunction "X3_12") (pintype "bidirectional"))
    )
    (net (code "22") (name "/Y4") (class "Default")
      (node (ref "D10") (pin "C") (pinfunction "C_C") (pintype "passive"))
      (node (ref "D106") (pin "C") (pinfunction "C_C") (pintype "passive"))
      (node (ref "D122") (pin "C") (pinfunction "C_C") (pintype "passive"))
      (node (ref "D26") (pin "C") (pinfunction "C_C") (pintype "passive"))
      (node (ref "D42") (pin "C") (pinfunction "C_C") (pintype "passive"))
      (node (ref "D58") (pin "C") (pinfunction "C_C") (pintype "passive"))
      (node (ref "D74") (pin "C") (pinfunction "C_C") (pintype "passive"))
      (node (ref "D90") (pin "C") (pinfunction "C_C") (pintype "passive"))
      (node (ref "IC3") (pin "1") (pinfunction "X4_1") (pintype "bidirectional"))
    )
    (net (code "23") (name "/Y5") (class "Default")
      (node (ref "D108") (pin "C") (pinfunction "C_C") (pintype "passive"))
      (node (ref "D12") (pin "C") (pinfunction "C_C") (pintype "passive"))
      (node (ref "D124") (pin "C") (pinfunction "C_C") (pintype "passive"))
      (node (ref "D28") (pin "C") (pinfunction "C_C") (pintype "passive"))
      (node (ref "D44") (pin "C") (pinfunction "C_C") (pintype "passive"))
      (node (ref "D60") (pin "C") (pinfunction "C_C") (pintype "passive"))
      (node (ref "D76") (pin "C") (pinfunction "C_C") (pintype "passive"))
      (node (ref "D92") (pin "C") (pinfunction "C_C") (pintype "passive"))
      (node (ref "IC3") (pin "5") (pinfunction "X5_5") (pintype "bidirectional"))
    )
    (net (code "24") (name "/Y6") (class "Default")
      (node (ref "D110") (pin "C") (pinfunction "C_C") (pintype "passive"))
      (node (ref "D126") (pin "C") (pinfunction "C_C") (pintype "passive"))
      (node (ref "D14") (pin "C") (pinfunction "C_C") (pintype "passive"))
      (node (ref "D30") (pin "C") (pinfunction "C_C") (pintype "passive"))
      (node (ref "D46") (pin "C") (pinfunction "C_C") (pintype "passive"))
      (node (ref "D62") (pin "C") (pinfunction "C_C") (pintype "passive"))
      (node (ref "D78") (pin "C") (pinfunction "C_C") (pintype "passive"))
      (node (ref "D94") (pin "C") (pinfunction "C_C") (pintype "passive"))
      (node (ref "IC3") (pin "2") (pinfunction "X6_2") (pintype "bidirectional"))
    )
    (net (code "25") (name "/Y7") (class "Default")
      (node (ref "D112") (pin "C") (pinfunction "C_C") (pintype "passive"))
      (node (ref "D128") (pin "C") (pinfunction "C_C") (pintype "passive"))
      (node (ref "D16") (pin "C") (pinfunction "C_C") (pintype "passive"))
      (node (ref "D32") (pin "C") (pinfunction "C_C") (pintype "passive"))
      (node (ref "D48") (pin "C") (pinfunction "C_C") (pintype "passive"))
      (node (ref "D64") (pin "C") (pinfunction "C_C") (pintype "passive"))
      (node (ref "D80") (pin "C") (pinfunction "C_C") (pintype "passive"))
      (node (ref "D96") (pin "C") (pinfunction "C_C") (pintype "passive"))
      (node (ref "IC3") (pin "4") (pinfunction "X7_4") (pintype "bidirectional"))
    )
    (net (code "26") (name "GND") (class "Default")
      (node (ref "C1") (pin "2") (pinfunction "2_2") (pintype "passive"))
      (node (ref "C2") (pin "2") (pinfunction "2_2") (pintype "passive"))
      (node (ref "C3") (pin "2") (pinfunction "2_2") (pintype "passive"))
      (node (ref "GND") (pin "1") (pinfunction "P_1") (pintype "passive"))
      (node (ref "IC1") (pin "11") (pinfunction "I_11") (pintype "input"))
      (node (ref "IC1") (pin "13") (pinfunction "I_13") (pintype "input"))
      (node (ref "IC1") (pin "7") (pinfunction "GND_7") (pintype "power_in"))
      (node (ref "IC1") (pin "9") (pinfunction "I_9") (pintype "input"))
      (node (ref "IC2") (pin "7") (pinfunction "VEE_7") (pintype "power_in"))
      (node (ref "IC2") (pin "8") (pinfunction "GND_8") (pintype "power_in"))
      (node (ref "IC3") (pin "7") (pinfunction "VEE_7") (pintype "power_in"))
      (node (ref "IC3") (pin "8") (pinfunction "GND_8") (pintype "power_in"))
    )
    (net (code "27") (name "Net-(DRIVE-P)") (class "Default")
      (node (ref "DRIVE") (pin "1") (pinfunction "P_1") (pintype "passive"))
      (node (ref "IC1") (pin "1") (pinfunction "I_1") (pintype "input"))
    )
    (net (code "28") (name "Net-(IC1A-O)") (class "Default")
      (node (ref "IC1") (pin "2") (pinfunction "O_2") (pintype "output"))
      (node (ref "IC2") (pin "3") (pinfunction "X_3") (pintype "bidirectional"))
      (node (ref "R3") (pin "1") (pinfunction "1_1") (pintype "passive"))
    )
    (net (code "29") (name "Net-(IC1B-I)") (class "Default")
      (node (ref "IC1") (pin "3") (pinfunction "I_3") (pintype "input"))
      (node (ref "R1") (pin "1") (pinfunction "1_1") (pintype "passive"))
      (node (ref "R2") (pin "1") (pinfunction "1_1") (pintype "passive"))
    )
    (net (code "30") (name "Net-(IC1B-O)") (class "Default")
      (node (ref "IC1") (pin "4") (pinfunction "O_4") (pintype "output"))
      (node (ref "IC1") (pin "5") (pinfunction "I_5") (pintype "input"))
    )
    (net (code "31") (name "Net-(IC1C-O)") (class "Default")
      (node (ref "IC1") (pin "6") (pinfunction "O_6") (pintype "output"))
      (node (ref "R2") (pin "2") (pinfunction "2_2") (pintype "passive"))
      (node (ref "SENSE") (pin "1") (pinfunction "P_1") (pintype "passive"))
    )
    (net (code "32") (name "Net-(IC3A-X)") (class "Default")
      (node (ref "IC3") (pin "3") (pinfunction "X_3") (pintype "bidirectional"))
      (node (ref "R1") (pin "2") (pinfunction "2_2") (pintype "passive"))
      (node (ref "R3") (pin "2") (pinfunction "2_2") (pintype "passive"))
    )
    (net (code "33") (name "Net-(KEY1-P)") (class "Default")
      (node (ref "D1") (pin "C") (pinfunction "C_C") (pintype "passive"))
      (node (ref "D2") (pin "A") (pinfunction "A_A") (pintype "passive"))
      (node (ref "KEY1") (pin "1") (pinfunction "P_1") (pintype "passive"))
    )
    (net (code "34") (name "Net-(KEY2-P)") (class "Default")
      (node (ref "D3") (pin "C") (pinfunction "C_C") (pintype "passive"))
      (node (ref "D4") (pin "A") (pinfunction "A_A") (pintype "passive"))
      (node (ref "KEY2") (pin "1") (pinfunction "P_1") (pintype "passive"))
    )
    (net (code "35") (name "Net-(KEY3-P)") (class "Default")
      (node (ref "D5") (pin "C") (pinfunction "C_C") (pintype "passive"))
      (node (ref "D6") (pin "A") (pinfunction "A_A") (pintype "passive"))
      (node (ref "KEY3") (pin "1") (pinfunction "P_1") (pintype "passive"))
    )
    (net (code "36") (name "Net-(KEY4-P)") (class "Default")
      (node (ref "D7") (pin "C") (pinfunction "C_C") (pintype "passive"))
      (node (ref "D8") (pin "A") (pinfunction "A_A") (pintype "passive"))
      (node (ref "KEY4") (pin "1") (pinfunction "P_1") (pintype "passive"))
    )
    (net (code "37") (name "Net-(KEY5-P)") (class "Default")
      (node (ref "D10") (pin "A") (pinfunction "A_A") (pintype "passive"))
      (node (ref "D9") (pin "C") (pinfunction "C_C") (pintype "passive"))
      (node (ref "KEY5") (pin "1") (pinfunction "P_1") (pintype "passive"))
    )
    (net (code "38") (name "Net-(KEY6-P)") (class "Default")
      (node (ref "D11") (pin "C") (pinfunction "C_C") (pintype "passive"))
      (node (ref "D12") (pin "A") (pinfunction "A_A") (pintype "passive"))
      (node (ref "KEY6") (pin "1") (pinfunction "P_1") (pintype "passive"))
    )
    (net (code "39") (name "Net-(KEY7-P)") (class "Default")
      (node (ref "D13") (pin "C") (pinfunction "C_C") (pintype "passive"))
      (node (ref "D14") (pin "A") (pinfunction "A_A") (pintype "passive"))
      (node (ref "KEY7") (pin "1") (pinfunction "P_1") (pintype "passive"))
    )
    (net (code "40") (name "Net-(KEY8-P)") (class "Default")
      (node (ref "D15") (pin "C") (pinfunction "C_C") (pintype "passive"))
      (node (ref "D16") (pin "A") (pinfunction "A_A") (pintype "passive"))
      (node (ref "KEY8") (pin "1") (pinfunction "P_1") (pintype "passive"))
    )
    (net (code "41") (name "Net-(KEY9-P)") (class "Default")
      (node (ref "D17") (pin "C") (pinfunction "C_C") (pintype "passive"))
      (node (ref "D18") (pin "A") (pinfunction "A_A") (pintype "passive"))
      (node (ref "KEY9") (pin "1") (pinfunction "P_1") (pintype "passive"))
    )
    (net (code "42") (name "Net-(KEY10-P)") (class "Default")
      (node (ref "D19") (pin "C") (pinfunction "C_C") (pintype "passive"))
      (node (ref "D20") (pin "A") (pinfunction "A_A") (pintype "passive"))
      (node (ref "KEY10") (pin "1") (pinfunction "P_1") (pintype "passive"))
    )
    (net (code "43") (name "Net-(KEY11-P)") (class "Default")
      (node (ref "D21") (pin "C") (pinfunction "C_C") (pintype "passive"))
      (node (ref "D22") (pin "A") (pinfunction "A_A") (pintype "passive"))
      (node (ref "KEY11") (pin "1") (pinfunction "P_1") (pintype "passive"))
    )
    (net (code "44") (name "Net-(KEY12-P)") (class "Default")
      (node (ref "D23") (pin "C") (pinfunction "C_C") (pintype "passive"))
      (node (ref "D24") (pin "A") (pinfunction "A_A") (pintype "passive"))
      (node (ref "KEY12") (pin "1") (pinfunction "P_1") (pintype "passive"))
    )
    (net (code "45") (name "Net-(KEY13-P)") (class "Default")
      (node (ref "D25") (pin "C") (pinfunction "C_C") (pintype "passive"))
      (node (ref "D26") (pin "A") (pinfunction "A_A") (pintype "passive"))
      (node (ref "KEY13") (pin "1") (pinfunction "P_1") (pintype "passive"))
    )
    (net (code "46") (name "Net-(KEY14-P)") (class "Default")
      (node (ref "D27") (pin "C") (pinfunction "C_C") (pintype "passive"))
      (node (ref "D28") (pin "A") (pinfunction "A_A") (pintype "passive"))
      (node (ref "KEY14") (pin "1") (pinfunction "P_1") (pintype "passive"))
    )
    (net (code "47") (name "Net-(KEY15-P)") (class "Default")
      (node (ref "D29") (pin "C") (pinfunction "C_C") (pintype "passive"))
      (node (ref "D30") (pin "A") (pinfunction "A_A") (pintype "passive"))
      (node (ref "KEY15") (pin "1") (pinfunction "P_1") (pintype "passive"))
    )
    (net (code "48") (name "Net-(KEY16-P)") (class "Default")
      (node (ref "D31") (pin "C") (pinfunction "C_C") (pintype "passive"))
      (node (ref "D32") (pin "A") (pinfunction "A_A") (pintype "passive"))
      (node (ref "KEY16") (pin "1") (pinfunction "P_1") (pintype "passive"))
    )
    (net (code "49") (name "Net-(KEY17-P)") (class "Default")
      (node (ref "D33") (pin "C") (pinfunction "C_C") (pintype "passive"))
      (node (ref "D34") (pin "A") (pinfunction "A_A") (pintype "passive"))
      (node (ref "KEY17") (pin "1") (pinfunction "P_1") (pintype "passive"))
    )
    (net (code "50") (name "Net-(KEY18-P)") (class "Default")
      (node (ref "D35") (pin "C") (pinfunction "C_C") (pintype "passive"))
      (node (ref "D36") (pin "A") (pinfunction "A_A") (pintype "passive"))
      (node (ref "KEY18") (pin "1") (pinfunction "P_1") (pintype "passive"))
    )
    (net (code "51") (name "Net-(KEY19-P)") (class "Default")
      (node (ref "D37") (pin "C") (pinfunction "C_C") (pintype "passive"))
      (node (ref "D38") (pin "A") (pinfunction "A_A") (pintype "passive"))
      (node (ref "KEY19") (pin "1") (pinfunction "P_1") (pintype "passive"))
    )
    (net (code "52") (name "Net-(KEY20-P)") (class "Default")
      (node (ref "D39") (pin "C") (pinfunction "C_C") (pintype "passive"))
      (node (ref "D40") (pin "A") (pinfunction "A_A") (pintype "passive"))
      (node (ref "KEY20") (pin "1") (pinfunction "P_1") (pintype "passive"))
    )
    (net (code "53") (name "Net-(KEY21-P)") (class "Default")
      (node (ref "D41") (pin "C") (pinfunction "C_C") (pintype "passive"))
      (node (ref "D42") (pin "A") (pinfunction "A_A") (pintype "passive"))
      (node (ref "KEY21") (pin "1") (pinfunction "P_1") (pintype "passive"))
    )
    (net (code "54") (name "Net-(KEY22-P)") (class "Default")
      (node (ref "D43") (pin "C") (pinfunction "C_C") (pintype "passive"))
      (node (ref "D44") (pin "A") (pinfunction "A_A") (pintype "passive"))
      (node (ref "KEY22") (pin "1") (pinfunction "P_1") (pintype "passive"))
    )
    (net (code "55") (name "Net-(KEY23-P)") (class "Default")
      (node (ref "D45") (pin "C") (pinfunction "C_C") (pintype "passive"))
      (node (ref "D46") (pin "A") (pinfunction "A_A") (pintype "passive"))
      (node (ref "KEY23") (pin "1") (pinfunction "P_1") (pintype "passive"))
    )
    (net (code "56") (name "Net-(KEY24-P)") (class "Default")
      (node (ref "D47") (pin "C") (pinfunction "C_C") (pintype "passive"))
      (node (ref "D48") (pin "A") (pinfunction "A_A") (pintype "passive"))
      (node (ref "KEY24") (pin "1") (pinfunction "P_1") (pintype "passive"))
    )
    (net (code "57") (name "Net-(KEY25-P)") (class "Default")
      (node (ref "D49") (pin "C") (pinfunction "C_C") (pintype "passive"))
      (node (ref "D50") (pin "A") (pinfunction "A_A") (pintype "passive"))
      (node (ref "KEY25") (pin "1") (pinfunction "P_1") (pintype "passive"))
    )
    (net (code "58") (name "Net-(KEY26-P)") (class "Default")
      (node (ref "D51") (pin "C") (pinfunction "C_C") (pintype "passive"))
      (node (ref "D52") (pin "A") (pinfunction "A_A") (pintype "passive"))
      (node (ref "KEY26") (pin "1") (pinfunction "P_1") (pintype "passive"))
    )
    (net (code "59") (name "Net-(KEY27-P)") (class "Default")
      (node (ref "D53") (pin "C") (pinfunction "C_C") (pintype "passive"))
      (node (ref "D54") (pin "A") (pinfunction "A_A") (pintype "passive"))
      (node (ref "KEY27") (pin "1") (pinfunction "P_1") (pintype "passive"))
    )
    (net (code "60") (name "Net-(KEY28-P)") (class "Default")
      (node (ref "D55") (pin "C") (pinfunction "C_C") (pintype "passive"))
      (node (ref "D56") (pin "A") (pinfunction "A_A") (pintype "passive"))
      (node (ref "KEY28") (pin "1") (pinfunction "P_1") (pintype "passive"))
    )
    (net (code "61") (name "Net-(KEY29-P)") (class "Default")
      (node (ref "D57") (pin "C") (pinfunction "C_C") (pintype "passive"))
      (node (ref "D58") (pin "A") (pinfunction "A_A") (pintype "passive"))
      (node (ref "KEY29") (pin "1") (pinfunction "P_1") (pintype "passive"))
    )
    (net (code "62") (name "Net-(KEY30-P)") (class "Default")
      (node (ref "D59") (pin "C") (pinfunction "C_C") (pintype "passive"))
      (node (ref "D60") (pin "A") (pinfunction "A_A") (pintype "passive"))
      (node (ref "KEY30") (pin "1") (pinfunction "P_1") (pintype "passive"))
    )
    (net (code "63") (name "Net-(KEY31-P)") (class "Default")
      (node (ref "D61") (pin "C") (pinfunction "C_C") (pintype "passive"))
      (node (ref "D62") (pin "A") (pinfunction "A_A") (pintype "passive"))
      (node (ref "KEY31") (pin "1") (pinfunction "P_1") (pintype "passive"))
    )
    (net (code "64") (name "Net-(KEY32-P)") (class "Default")
      (node (ref "D63") (pin "C") (pinfunction "C_C") (pintype "passive"))
      (node (ref "D64") (pin "A") (pinfunction "A_A") (pintype "passive"))
      (node (ref "KEY32") (pin "1") (pinfunction "P_1") (pintype "passive"))
    )
    (net (code "65") (name "Net-(KEY33-P)") (class "Default")
      (node (ref "D65") (pin "C") (pinfunction "C_C") (pintype "passive"))
      (node (ref "D66") (pin "A") (pinfunction "A_A") (pintype "passive"))
      (node (ref "KEY33") (pin "1") (pinfunction "P_1") (pintype "passive"))
    )
    (net (code "66") (name "Net-(KEY34-P)") (class "Default")
      (node (ref "D67") (pin "C") (pinfunction "C_C") (pintype "passive"))
      (node (ref "D68") (pin "A") (pinfunction "A_A") (pintype "passive"))
      (node (ref "KEY34") (pin "1") (pinfunction "P_1") (pintype "passive"))
    )
    (net (code "67") (name "Net-(KEY35-P)") (class "Default")
      (node (ref "D69") (pin "C") (pinfunction "C_C") (pintype "passive"))
      (node (ref "D70") (pin "A") (pinfunction "A_A") (pintype "passive"))
      (node (ref "KEY35") (pin "1") (pinfunction "P_1") (pintype "passive"))
    )
    (net (code "68") (name "Net-(KEY36-P)") (class "Default")
      (node (ref "D71") (pin "C") (pinfunction "C_C") (pintype "passive"))
      (node (ref "D72") (pin "A") (pinfunction "A_A") (pintype "passive"))
      (node (ref "KEY36") (pin "1") (pinfunction "P_1") (pintype "passive"))
    )
    (net (code "69") (name "Net-(KEY37-P)") (class "Default")
      (node (ref "D73") (pin "C") (pinfunction "C_C") (pintype "passive"))
      (node (ref "D74") (pin "A") (pinfunction "A_A") (pintype "passive"))
      (node (ref "KEY37") (pin "1") (pinfunction "P_1") (pintype "passive"))
    )
    (net (code "70") (name "Net-(KEY38-P)") (class "Default")
      (node (ref "D75") (pin "C") (pinfunction "C_C") (pintype "passive"))
      (node (ref "D76") (pin "A") (pinfunction "A_A") (pintype "passive"))
      (node (ref "KEY38") (pin "1") (pinfunction "P_1") (pintype "passive"))
    )
    (net (code "71") (name "Net-(KEY39-P)") (class "Default")
      (node (ref "D77") (pin "C") (pinfunction "C_C") (pintype "passive"))
      (node (ref "D78") (pin "A") (pinfunction "A_A") (pintype "passive"))
      (node (ref "KEY39") (pin "1") (pinfunction "P_1") (pintype "passive"))
    )
    (net (code "72") (name "Net-(KEY40-P)") (class "Default")
      (node (ref "D79") (pin "C") (pinfunction "C_C") (pintype "passive"))
      (node (ref "D80") (pin "A") (pinfunction "A_A") (pintype "passive"))
      (node (ref "KEY40") (pin "1") (pinfunction "P_1") (pintype "passive"))
    )
    (net (code "73") (name "Net-(KEY41-P)") (class "Default")
      (node (ref "D81") (pin "C") (pinfunction "C_C") (pintype "passive"))
      (node (ref "D82") (pin "A") (pinfunction "A_A") (pintype "passive"))
      (node (ref "KEY41") (pin "1") (pinfunction "P_1") (pintype "passive"))
    )
    (net (code "74") (name "Net-(KEY42-P)") (class "Default")
      (node (ref "D83") (pin "C") (pinfunction "C_C") (pintype "passive"))
      (node (ref "D84") (pin "A") (pinfunction "A_A") (pintype "passive"))
      (node (ref "KEY42") (pin "1") (pinfunction "P_1") (pintype "passive"))
    )
    (net (code "75") (name "Net-(KEY43-P)") (class "Default")
      (node (ref "D85") (pin "C") (pinfunction "C_C") (pintype "passive"))
      (node (ref "D86") (pin "A") (pinfunction "A_A") (pintype "passive"))
      (node (ref "KEY43") (pin "1") (pinfunction "P_1") (pintype "passive"))
    )
    (net (code "76") (name "Net-(KEY44-P)") (class "Default")
      (node (ref "D87") (pin "C") (pinfunction "C_C") (pintype "passive"))
      (node (ref "D88") (pin "A") (pinfunction "A_A") (pintype "passive"))
      (node (ref "KEY44") (pin "1") (pinfunction "P_1") (pintype "passive"))
    )
    (net (code "77") (name "Net-(KEY45-P)") (class "Default")
      (node (ref "D89") (pin "C") (pinfunction "C_C") (pintype "passive"))
      (node (ref "D90") (pin "A") (pinfunction "A_A") (pintype "passive"))
      (node (ref "KEY45") (pin "1") (pinfunction "P_1") (pintype "passive"))
    )
    (net (code "78") (name "Net-(KEY46-P)") (class "Default")
      (node (ref "D91") (pin "C") (pinfunction "C_C") (pintype "passive"))
      (node (ref "D92") (pin "A") (pinfunction "A_A") (pintype "passive"))
      (node (ref "KEY46") (pin "1") (pinfunction "P_1") (pintype "passive"))
    )
    (net (code "79") (name "Net-(KEY47-P)") (class "Default")
      (node (ref "D93") (pin "C") (pinfunction "C_C") (pintype "passive"))
      (node (ref "D94") (pin "A") (pinfunction "A_A") (pintype "passive"))
      (node (ref "KEY47") (pin "1") (pinfunction "P_1") (pintype "passive"))
    )
    (net (code "80") (name "Net-(KEY48-P)") (class "Default")
      (node (ref "D95") (pin "C") (pinfunction "C_C") (pintype "passive"))
      (node (ref "D96") (pin "A") (pinfunction "A_A") (pintype "passive"))
      (node (ref "KEY48") (pin "1") (pinfunction "P_1") (pintype "passive"))
    )
    (net (code "81") (name "Net-(KEY49-P)") (class "Default")
      (node (ref "D97") (pin "C") (pinfunction "C_C") (pintype "passive"))
      (node (ref "D98") (pin "A") (pinfunction "A_A") (pintype "passive"))
      (node (ref "KEY49") (pin "1") (pinfunction "P_1") (pintype "passive"))
    )
    (net (code "82") (name "Net-(KEY50-P)") (class "Default")
      (node (ref "D100") (pin "A") (pinfunction "A_A") (pintype "passive"))
      (node (ref "D99") (pin "C") (pinfunction "C_C") (pintype "passive"))
      (node (ref "KEY50") (pin "1") (pinfunction "P_1") (pintype "passive"))
    )
    (net (code "83") (name "Net-(KEY51-P)") (class "Default")
      (node (ref "D101") (pin "C") (pinfunction "C_C") (pintype "passive"))
      (node (ref "D102") (pin "A") (pinfunction "A_A") (pintype "passive"))
      (node (ref "KEY51") (pin "1") (pinfunction "P_1") (pintype "passive"))
    )
    (net (code "84") (name "Net-(KEY52-P)") (class "Default")
      (node (ref "D103") (pin "C") (pinfunction "C_C") (pintype "passive"))
      (node (ref "D104") (pin "A") (pinfunction "A_A") (pintype "passive"))
      (node (ref "KEY52") (pin "1") (pinfunction "P_1") (pintype "passive"))
    )
    (net (code "85") (name "Net-(KEY53-P)") (class "Default")
      (node (ref "D105") (pin "C") (pinfunction "C_C") (pintype "passive"))
      (node (ref "D106") (pin "A") (pinfunction "A_A") (pintype "passive"))
      (node (ref "KEY53") (pin "1") (pinfunction "P_1") (pintype "passive"))
    )
    (net (code "86") (name "Net-(KEY54-P)") (class "Default")
      (node (ref "D107") (pin "C") (pinfunction "C_C") (pintype "passive"))
      (node (ref "D108") (pin "A") (pinfunction "A_A") (pintype "passive"))
      (node (ref "KEY54") (pin "1") (pinfunction "P_1") (pintype "passive"))
    )
    (net (code "87") (name "Net-(KEY55-P)") (class "Default")
      (node (ref "D109") (pin "C") (pinfunction "C_C") (pintype "passive"))
      (node (ref "D110") (pin "A") (pinfunction "A_A") (pintype "passive"))
      (node (ref "KEY55") (pin "1") (pinfunction "P_1") (pintype "passive"))
    )
    (net (code "88") (name "Net-(KEY56-P)") (class "Default")
      (node (ref "D111") (pin "C") (pinfunction "C_C") (pintype "passive"))
      (node (ref "D112") (pin "A") (pinfunction "A_A") (pintype "passive"))
      (node (ref "KEY56") (pin "1") (pinfunction "P_1") (pintype "passive"))
    )
    (net (code "89") (name "Net-(KEY57-P)") (class "Default")
      (node (ref "D113") (pin "C") (pinfunction "C_C") (pintype "passive"))
      (node (ref "D114") (pin "A") (pinfunction "A_A") (pintype "passive"))
      (node (ref "KEY57") (pin "1") (pinfunction "P_1") (pintype "passive"))
    )
    (net (code "90") (name "Net-(KEY58-P)") (class "Default")
      (node (ref "D115") (pin "C") (pinfunction "C_C") (pintype "passive"))
      (node (ref "D116") (pin "A") (pinfunction "A_A") (pintype "passive"))
      (node (ref "KEY58") (pin "1") (pinfunction "P_1") (pintype "passive"))
    )
    (net (code "91") (name "Net-(KEY59-P)") (class "Default")
      (node (ref "D117") (pin "C") (pinfunction "C_C") (pintype "passive"))
      (node (ref "D118") (pin "A") (pinfunction "A_A") (pintype "passive"))
      (node (ref "KEY59") (pin "1") (pinfunction "P_1") (pintype "passive"))
    )
    (net (code "92") (name "Net-(KEY60-P)") (class "Default")
      (node (ref "D119") (pin "C") (pinfunction "C_C") (pintype "passive"))
      (node (ref "D120") (pin "A") (pinfunction "A_A") (pintype "passive"))
      (node (ref "KEY60") (pin "1") (pinfunction "P_1") (pintype "passive"))
    )
    (net (code "93") (name "Net-(KEY61-P)") (class "Default")
      (node (ref "D121") (pin "C") (pinfunction "C_C") (pintype "passive"))
      (node (ref "D122") (pin "A") (pinfunction "A_A") (pintype "passive"))
      (node (ref "KEY61") (pin "1") (pinfunction "P_1") (pintype "passive"))
    )
    (net (code "94") (name "Net-(KEY62-P)") (class "Default")
      (node (ref "D123") (pin "C") (pinfunction "C_C") (pintype "passive"))
      (node (ref "D124") (pin "A") (pinfunction "A_A") (pintype "passive"))
      (node (ref "KEY62") (pin "1") (pinfunction "P_1") (pintype "passive"))
    )
    (net (code "95") (name "Net-(KEY63-P)") (class "Default")
      (node (ref "D125") (pin "C") (pinfunction "C_C") (pintype "passive"))
      (node (ref "D126") (pin "A") (pinfunction "A_A") (pintype "passive"))
      (node (ref "KEY63") (pin "1") (pinfunction "P_1") (pintype "passive"))
    )
    (net (code "96") (name "Net-(KEY64-P)") (class "Default")
      (node (ref "D127") (pin "C") (pinfunction "C_C") (pintype "passive"))
      (node (ref "D128") (pin "A") (pinfunction "A_A") (pintype "passive"))
      (node (ref "KEY64") (pin "1") (pinfunction "P_1") (pintype "passive"))
    )
    (net (code "97") (name "unconnected-(IC1D-O-Pad8)") (class "Default")
      (node (ref "IC1") (pin "8") (pinfunction "O_8") (pintype "output"))
    )
    (net (code "98") (name "unconnected-(IC1E-O-Pad10)") (class "Default")
      (node (ref "IC1") (pin "10") (pinfunction "O_10") (pintype "output"))
    )
    (net (code "99") (name "unconnected-(IC1F-O-Pad12)") (class "Default")
      (node (ref "IC1") (pin "12") (pinfunction "O_12") (pintype "output"))
    )
  )
)
